# EnvironmentMonitorV3.net
KiCad netlist of a schematic drawn in EAGLE
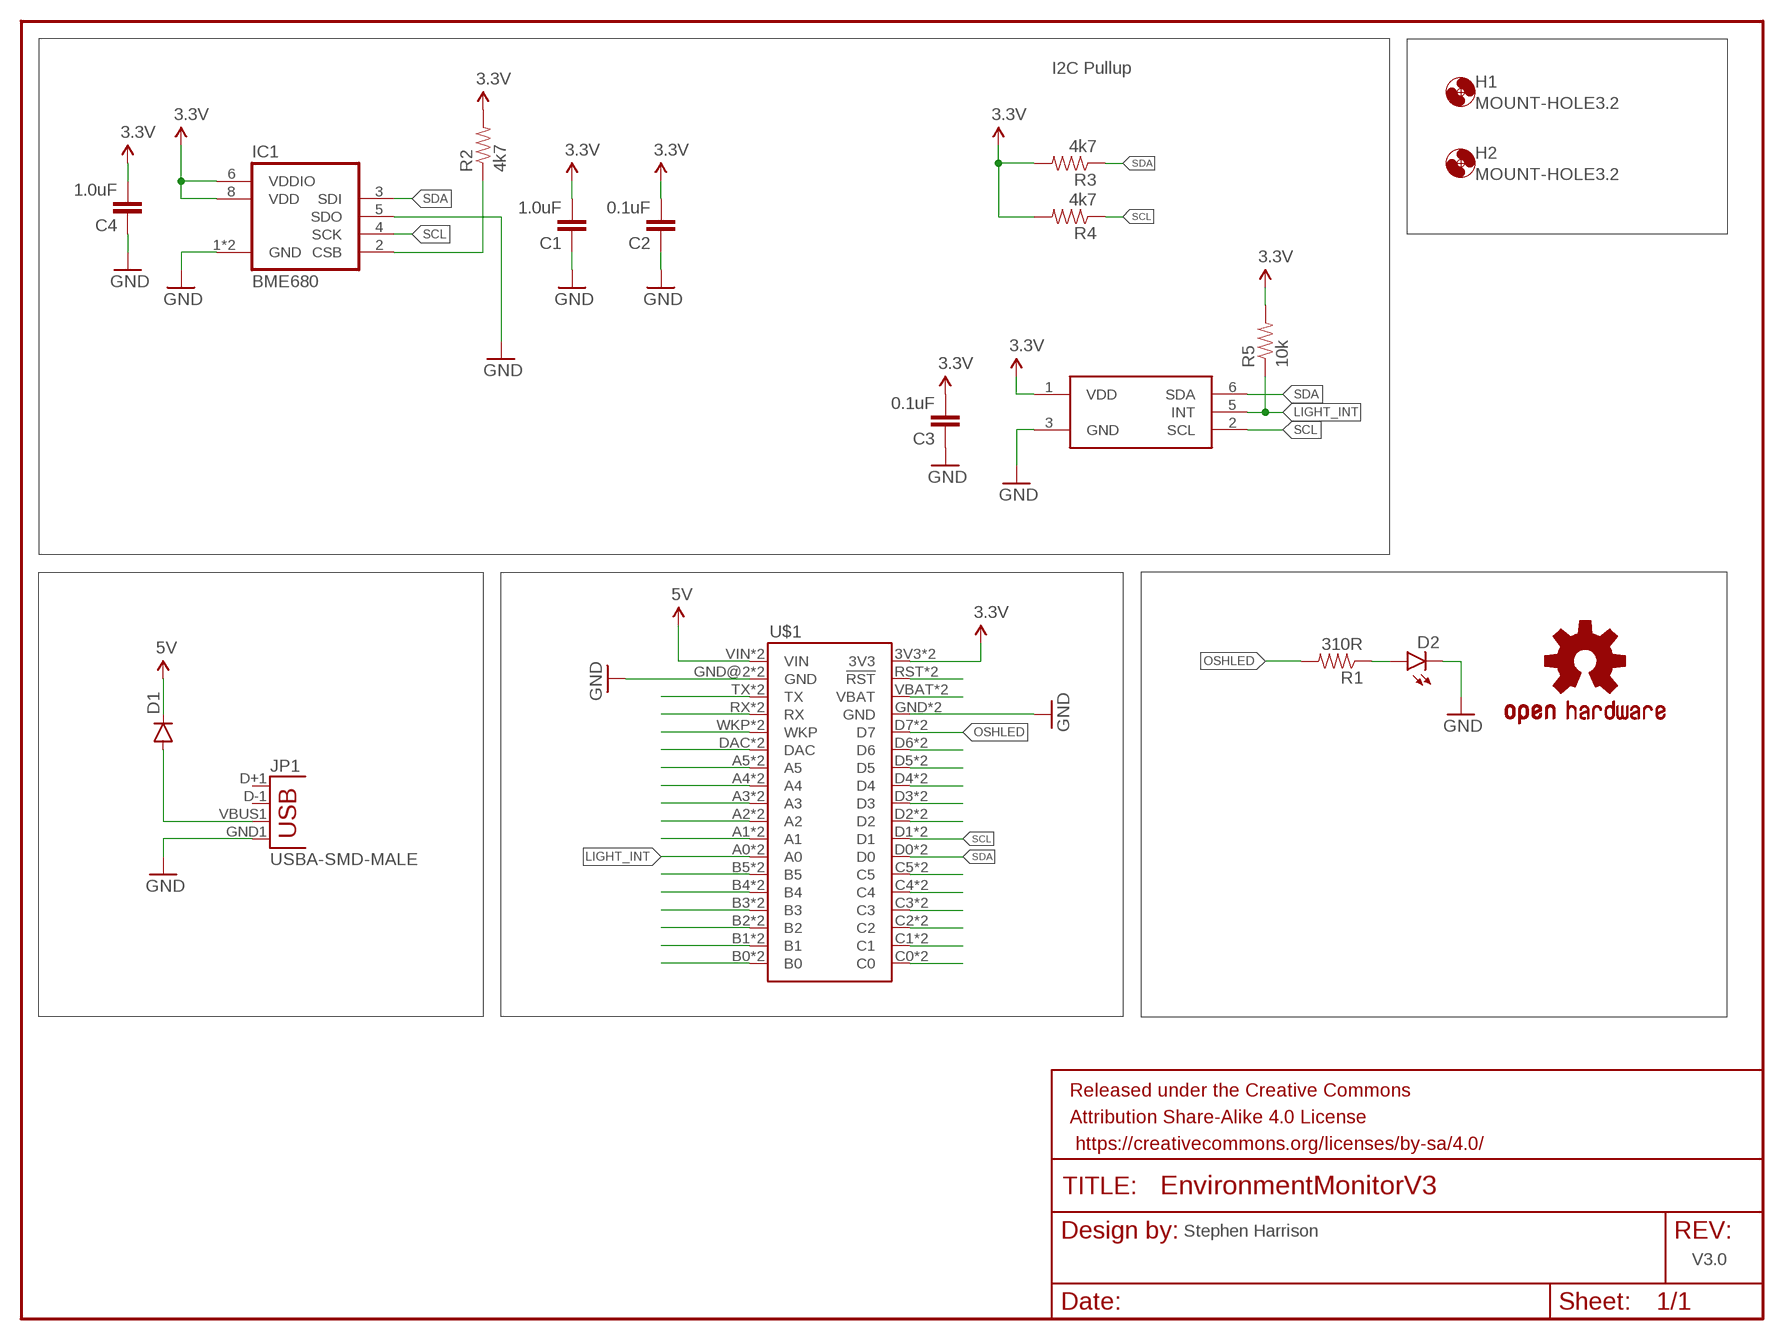
[diagram p0: schematic, sheet 1]

(export (version "E")
  (design (tool "Eeschema 10.0.6"))
  (components
    (comp (ref "C1")
      (value "1.0uF")
      (footprint "eagle-import:0805-CAP")
      (libsource (lib "eagle-import") (part "1.0UF-25V-+80/-20(0805){dblquote}"))
    )
    (comp (ref "C2")
      (value "0.1uF")
      (footprint "eagle-import:0805-CAP")
      (libsource (lib "eagle-import") (part "1.0UF-25V-+80/-20(0805){dblquote}"))
    )
    (comp (ref "C3")
      (value "0.1uF")
      (footprint "eagle-import:0805-CAP")
      (libsource (lib "eagle-import") (part "1.0UF-25V-+80/-20(0805){dblquote}"))
    )
    (comp (ref "C4")
      (value "1.0uF")
      (footprint "eagle-import:0805-CAP")
      (libsource (lib "eagle-import") (part "1.0UF-25V-+80/-20(0805){dblquote}"))
    )
    (comp (ref "D1")
      (value "DIODESMA")
      (footprint "eagle-import:SMA-DIODE")
      (libsource (lib "eagle-import") (part "DIODESMA"))
    )
    (comp (ref "D2")
      (value "LED1206-BOTTOM")
      (footprint "eagle-import:LED-1206-BOTTOM")
      (libsource (lib "eagle-import") (part "LED1206-BOTTOM"))
    )
    (comp (ref "FRAME1")
      (value "FRAME-LETTER")
      (footprint "eagle-import:CREATIVE_COMMONS")
      (libsource (lib "eagle-import") (part "FRAME-LETTER"))
    )
    (comp (ref "H1")
      (value "MOUNT-HOLE3.2")
      (footprint "eagle-import:3,2")
      (libsource (lib "eagle-import") (part "MOUNT-HOLE3.2"))
    )
    (comp (ref "H2")
      (value "MOUNT-HOLE3.2")
      (footprint "eagle-import:3,2")
      (libsource (lib "eagle-import") (part "MOUNT-HOLE3.2"))
    )
    (comp (ref "IC1")
      (value "BME680")
      (footprint "eagle-import:BME680")
      (libsource (lib "eagle-import") (part "BME680"))
    )
    (comp (ref "JP1")
      (value "USBA-SMD-MALE")
      (footprint "eagle-import:USB-A-SMT-MALE")
      (libsource (lib "eagle-import") (part "USBA-SMD-MALE"))
    )
    (comp (ref "LOGO1")
      (value "OSHW-LOGOM")
      (footprint "eagle-import:OSHW-LOGO-M")
      (libsource (lib "eagle-import") (part "OSHW-LOGOM"))
    )
    (comp (ref "R1")
      (value "310R")
      (footprint "eagle-import:0805")
      (libsource (lib "eagle-import") (part "RESISTOR0805-RES"))
    )
    (comp (ref "R2")
      (value "4k7")
      (footprint "eagle-import:0805")
      (libsource (lib "eagle-import") (part "RESISTOR0805-RES"))
    )
    (comp (ref "R3")
      (value "4k7")
      (footprint "eagle-import:0805")
      (libsource (lib "eagle-import") (part "RESISTOR0805-RES"))
    )
    (comp (ref "R4")
      (value "4k7")
      (footprint "eagle-import:0805")
      (libsource (lib "eagle-import") (part "RESISTOR0805-RES"))
    )
    (comp (ref "R5")
      (value "10k")
      (footprint "eagle-import:0805")
      (libsource (lib "eagle-import") (part "RESISTOR0805-RES"))
    )
    (comp (ref "U$1")
      (value "ELECTRONDUALNAMED")
      (footprint "eagle-import:ELECTRON_SIMPLE_SILK_NAMES_DUAL")
      (libsource (lib "eagle-import") (part "ELECTRONDUALNAMED"))
    )
    (comp (ref "U$2")
      (value "TCS3472")
      (footprint "eagle-import:FN-6")
      (libsource (lib "eagle-import") (part "TCS3472"))
    )
  )
  (nets
    (net (code "1") (name "3.3V") (class "Default")
      (node (ref "C1") (pin "2") (pinfunction "2_2") (pintype "passive"))
      (node (ref "C2") (pin "2") (pinfunction "2_2") (pintype "passive"))
      (node (ref "C3") (pin "2") (pinfunction "2_2") (pintype "passive"))
      (node (ref "C4") (pin "2") (pinfunction "2_2") (pintype "passive"))
      (node (ref "IC1") (pin "6") (pinfunction "VDDIO_6") (pintype "power_in"))
      (node (ref "IC1") (pin "8") (pinfunction "VDD_8") (pintype "power_in"))
      (node (ref "R2") (pin "2") (pinfunction "2_2") (pintype "passive"))
      (node (ref "R3") (pin "2") (pinfunction "2_2") (pintype "passive"))
      (node (ref "R4") (pin "2") (pinfunction "2_2") (pintype "passive"))
      (node (ref "R5") (pin "2") (pinfunction "2_2") (pintype "passive"))
      (node (ref "U$1") (pin "3V3") (pinfunction "3V3_3V3") (pintype "power_in"))
      (node (ref "U$1") (pin "3V3_1") (pinfunction "3V3_3V3_1") (pintype "power_in"))
      (node (ref "U$2") (pin "1") (pinfunction "VDD_1") (pintype "bidirectional"))
    )
    (net (code "2") (name "5V") (class "Default")
      (node (ref "D1") (pin "C") (pinfunction "C_C") (pintype "passive"))
      (node (ref "U$1") (pin "VIN") (pinfunction "VIN_VIN") (pintype "power_in"))
      (node (ref "U$1") (pin "VIN_1B") (pinfunction "VIN_VIN_1B") (pintype "power_in"))
    )
    (net (code "3") (name "GND") (class "Default")
      (node (ref "C1") (pin "1") (pinfunction "1_1") (pintype "passive"))
      (node (ref "C2") (pin "1") (pinfunction "1_1") (pintype "passive"))
      (node (ref "C3") (pin "1") (pinfunction "1_1") (pintype "passive"))
      (node (ref "C4") (pin "1") (pinfunction "1_1") (pintype "passive"))
      (node (ref "D2") (pin "C") (pinfunction "C_C") (pintype "passive"))
      (node (ref "IC1") (pin "1") (pinfunction "GND_1") (pintype "power_in"))
      (node (ref "IC1") (pin "5") (pinfunction "SDO_5") (pintype "output"))
      (node (ref "IC1") (pin "7") (pinfunction "GND_7") (pintype "power_in"))
      (node (ref "JP1") (pin "GND1") (pinfunction "GND_GND1") (pintype "bidirectional"))
      (node (ref "U$1") (pin "GND") (pinfunction "GND_GND") (pintype "power_in"))
      (node (ref "U$1") (pin "GND@2") (pinfunction "GND_GND@2") (pintype "power_in"))
      (node (ref "U$1") (pin "GND_1") (pinfunction "GND_GND_1") (pintype "power_in"))
      (node (ref "U$1") (pin "GND_1B") (pinfunction "GND_GND_1B") (pintype "power_in"))
      (node (ref "U$2") (pin "3") (pinfunction "GND_3") (pintype "bidirectional"))
    )
    (net (code "4") (name "LIGHT_INT") (class "Default")
      (node (ref "R5") (pin "1") (pinfunction "1_1") (pintype "passive"))
      (node (ref "U$1") (pin "A0") (pinfunction "A0_A0") (pintype "bidirectional"))
      (node (ref "U$1") (pin "A0_1") (pinfunction "A0_A0_1") (pintype "bidirectional"))
      (node (ref "U$2") (pin "5") (pinfunction "INT_5") (pintype "bidirectional"))
    )
    (net (code "5") (name "Net-(D2-PadA)") (class "Default")
      (node (ref "D2") (pin "A") (pinfunction "A_A") (pintype "passive"))
      (node (ref "R1") (pin "1") (pinfunction "1_1") (pintype "passive"))
    )
    (net (code "6") (name "Net-(IC1-CSB)") (class "Default")
      (node (ref "IC1") (pin "2") (pinfunction "CSB_2") (pintype "input"))
      (node (ref "R2") (pin "1") (pinfunction "1_1") (pintype "passive"))
    )
    (net (code "7") (name "Net-(JP1-VBUS)") (class "Default")
      (node (ref "D1") (pin "A") (pinfunction "A_A") (pintype "passive"))
      (node (ref "JP1") (pin "VBUS1") (pinfunction "VBUS_VBUS1") (pintype "bidirectional"))
    )
    (net (code "8") (name "Net-(U$1-A1-PadA1_1)") (class "Default")
      (node (ref "U$1") (pin "A1") (pinfunction "A1_A1") (pintype "bidirectional"))
      (node (ref "U$1") (pin "A1_1") (pinfunction "A1_A1_1") (pintype "bidirectional"))
    )
    (net (code "9") (name "Net-(U$1-A2-PadA2_1)") (class "Default")
      (node (ref "U$1") (pin "A2") (pinfunction "A2_A2") (pintype "bidirectional"))
      (node (ref "U$1") (pin "A2_1") (pinfunction "A2_A2_1") (pintype "bidirectional"))
    )
    (net (code "10") (name "Net-(U$1-A3-PadA3_1)") (class "Default")
      (node (ref "U$1") (pin "A3") (pinfunction "A3_A3") (pintype "bidirectional"))
      (node (ref "U$1") (pin "A3_1") (pinfunction "A3_A3_1") (pintype "bidirectional"))
    )
    (net (code "11") (name "Net-(U$1-A4-PadA4_1)") (class "Default")
      (node (ref "U$1") (pin "A4") (pinfunction "A4_A4") (pintype "bidirectional"))
      (node (ref "U$1") (pin "A4_1") (pinfunction "A4_A4_1") (pintype "bidirectional"))
    )
    (net (code "12") (name "Net-(U$1-A5-PadA5_1)") (class "Default")
      (node (ref "U$1") (pin "A5") (pinfunction "A5_A5") (pintype "bidirectional"))
      (node (ref "U$1") (pin "A5_1") (pinfunction "A5_A5_1") (pintype "bidirectional"))
    )
    (net (code "13") (name "Net-(U$1-B0-PadB0_1)") (class "Default")
      (node (ref "U$1") (pin "B0") (pinfunction "B0_B0") (pintype "bidirectional"))
      (node (ref "U$1") (pin "B0_1") (pinfunction "B0_B0_1") (pintype "bidirectional"))
    )
    (net (code "14") (name "Net-(U$1-B1-PadB1_1)") (class "Default")
      (node (ref "U$1") (pin "B1") (pinfunction "B1_B1") (pintype "bidirectional"))
      (node (ref "U$1") (pin "B1_1") (pinfunction "B1_B1_1") (pintype "bidirectional"))
    )
    (net (code "15") (name "Net-(U$1-B2-PadB2_1)") (class "Default")
      (node (ref "U$1") (pin "B2") (pinfunction "B2_B2") (pintype "bidirectional"))
      (node (ref "U$1") (pin "B2_1") (pinfunction "B2_B2_1") (pintype "bidirectional"))
    )
    (net (code "16") (name "Net-(U$1-B3-PadB3_1)") (class "Default")
      (node (ref "U$1") (pin "B3") (pinfunction "B3_B3") (pintype "bidirectional"))
      (node (ref "U$1") (pin "B3_1") (pinfunction "B3_B3_1") (pintype "bidirectional"))
    )
    (net (code "17") (name "Net-(U$1-B4-PadB4_1)") (class "Default")
      (node (ref "U$1") (pin "B4") (pinfunction "B4_B4") (pintype "bidirectional"))
      (node (ref "U$1") (pin "B4_1") (pinfunction "B4_B4_1") (pintype "bidirectional"))
    )
    (net (code "18") (name "Net-(U$1-B5-PadB5_1)") (class "Default")
      (node (ref "U$1") (pin "B5") (pinfunction "B5_B5") (pintype "bidirectional"))
      (node (ref "U$1") (pin "B5_1") (pinfunction "B5_B5_1") (pintype "bidirectional"))
    )
    (net (code "19") (name "Net-(U$1-C0-PadC0_1)") (class "Default")
      (node (ref "U$1") (pin "C0") (pinfunction "C0_C0") (pintype "bidirectional"))
      (node (ref "U$1") (pin "C0_1") (pinfunction "C0_C0_1") (pintype "bidirectional"))
    )
    (net (code "20") (name "Net-(U$1-C1-PadC1_1)") (class "Default")
      (node (ref "U$1") (pin "C1") (pinfunction "C1_C1") (pintype "bidirectional"))
      (node (ref "U$1") (pin "C1_1") (pinfunction "C1_C1_1") (pintype "bidirectional"))
    )
    (net (code "21") (name "Net-(U$1-C2-PadC2_1)") (class "Default")
      (node (ref "U$1") (pin "C2") (pinfunction "C2_C2") (pintype "bidirectional"))
      (node (ref "U$1") (pin "C2_1") (pinfunction "C2_C2_1") (pintype "bidirectional"))
    )
    (net (code "22") (name "Net-(U$1-C3-PadC3_1)") (class "Default")
      (node (ref "U$1") (pin "C3") (pinfunction "C3_C3") (pintype "bidirectional"))
      (node (ref "U$1") (pin "C3_1") (pinfunction "C3_C3_1") (pintype "bidirectional"))
    )
    (net (code "23") (name "Net-(U$1-C4-PadC4_1)") (class "Default")
      (node (ref "U$1") (pin "C4") (pinfunction "C4_C4") (pintype "bidirectional"))
      (node (ref "U$1") (pin "C4_1") (pinfunction "C4_C4_1") (pintype "bidirectional"))
    )
    (net (code "24") (name "Net-(U$1-C5-PadC5_1)") (class "Default")
      (node (ref "U$1") (pin "C5") (pinfunction "C5_C5") (pintype "bidirectional"))
      (node (ref "U$1") (pin "C5_1") (pinfunction "C5_C5_1") (pintype "bidirectional"))
    )
    (net (code "25") (name "Net-(U$1-D2-PadD2_1)") (class "Default")
      (node (ref "U$1") (pin "D2") (pinfunction "D2_D2") (pintype "bidirectional"))
      (node (ref "U$1") (pin "D2_1") (pinfunction "D2_D2_1") (pintype "bidirectional"))
    )
    (net (code "26") (name "Net-(U$1-D3-PadD3_1)") (class "Default")
      (node (ref "U$1") (pin "D3") (pinfunction "D3_D3") (pintype "bidirectional"))
      (node (ref "U$1") (pin "D3_1") (pinfunction "D3_D3_1") (pintype "bidirectional"))
    )
    (net (code "27") (name "Net-(U$1-D4-PadD4_1)") (class "Default")
      (node (ref "U$1") (pin "D4") (pinfunction "D4_D4") (pintype "bidirectional"))
      (node (ref "U$1") (pin "D4_1") (pinfunction "D4_D4_1") (pintype "bidirectional"))
    )
    (net (code "28") (name "Net-(U$1-D5-PadD5_1)") (class "Default")
      (node (ref "U$1") (pin "D5") (pinfunction "D5_D5") (pintype "bidirectional"))
      (node (ref "U$1") (pin "D5_1") (pinfunction "D5_D5_1") (pintype "bidirectional"))
    )
    (net (code "29") (name "Net-(U$1-D6-PadD6_1)") (class "Default")
      (node (ref "U$1") (pin "D6") (pinfunction "D6_D6") (pintype "bidirectional"))
      (node (ref "U$1") (pin "D6_1") (pinfunction "D6_D6_1") (pintype "bidirectional"))
    )
    (net (code "30") (name "Net-(U$1-DAC-PadDAC_1)") (class "Default")
      (node (ref "U$1") (pin "DAC") (pinfunction "DAC_DAC") (pintype "bidirectional"))
      (node (ref "U$1") (pin "DAC_1") (pinfunction "DAC_DAC_1") (pintype "bidirectional"))
    )
    (net (code "31") (name "Net-(U$1-PadRX)") (class "Default")
      (node (ref "U$1") (pin "RX") (pinfunction "RX_RX") (pintype "bidirectional"))
      (node (ref "U$1") (pin "RX_1") (pinfunction "RX_RX_1") (pintype "bidirectional"))
    )
    (net (code "32") (name "Net-(U$1-PadTX)") (class "Default")
      (node (ref "U$1") (pin "TX") (pinfunction "TX_TX") (pintype "bidirectional"))
      (node (ref "U$1") (pin "TX_1") (pinfunction "TX_TX_1") (pintype "bidirectional"))
    )
    (net (code "33") (name "Net-(U$1-PadVBAT)") (class "Default")
      (node (ref "U$1") (pin "VBAT") (pinfunction "VBAT_VBAT") (pintype "passive"))
      (node (ref "U$1") (pin "VBATT_1") (pinfunction "VBAT_VBATT_1") (pintype "passive"))
    )
    (net (code "34") (name "Net-(U$1-PadWKP)") (class "Default")
      (node (ref "U$1") (pin "WKP") (pinfunction "WKP_WKP") (pintype "bidirectional"))
      (node (ref "U$1") (pin "WKP_1") (pinfunction "WKP_WKP_1") (pintype "bidirectional"))
    )
    (net (code "35") (name "Net-(U$1-~{RST}-PadRST)") (class "Default")
      (node (ref "U$1") (pin "RST") (pinfunction "~{RST}_RST") (pintype "bidirectional"))
      (node (ref "U$1") (pin "RST_1") (pinfunction "~{RST}_RST_1") (pintype "bidirectional"))
    )
    (net (code "36") (name "OSHLED") (class "Default")
      (node (ref "R1") (pin "2") (pinfunction "2_2") (pintype "passive"))
      (node (ref "U$1") (pin "D7") (pinfunction "D7_D7") (pintype "bidirectional"))
      (node (ref "U$1") (pin "D7_1") (pinfunction "D7_D7_1") (pintype "bidirectional"))
    )
    (net (code "37") (name "SCL") (class "Default")
      (node (ref "IC1") (pin "4") (pinfunction "SCK_4") (pintype "input"))
      (node (ref "R4") (pin "1") (pinfunction "1_1") (pintype "passive"))
      (node (ref "U$1") (pin "D1") (pinfunction "D1_D1") (pintype "bidirectional"))
      (node (ref "U$1") (pin "D1_1") (pinfunction "D1_D1_1") (pintype "bidirectional"))
      (node (ref "U$2") (pin "2") (pinfunction "SCL_2") (pintype "bidirectional"))
    )
    (net (code "38") (name "SDA") (class "Default")
      (node (ref "IC1") (pin "3") (pinfunction "SDI_3") (pintype "input"))
      (node (ref "R3") (pin "1") (pinfunction "1_1") (pintype "passive"))
      (node (ref "U$1") (pin "D0") (pinfunction "D0_D0") (pintype "bidirectional"))
      (node (ref "U$1") (pin "D0_1") (pinfunction "D0_D0_1") (pintype "bidirectional"))
      (node (ref "U$2") (pin "6") (pinfunction "SDA_6") (pintype "bidirectional"))
    )
    (net (code "39") (name "unconnected-(JP1-D+-PadD+1)") (class "Default")
      (node (ref "JP1") (pin "D+1") (pinfunction "D+_D+1") (pintype "bidirectional"))
    )
    (net (code "40") (name "unconnected-(JP1-D--PadD-1)") (class "Default")
      (node (ref "JP1") (pin "D-1") (pinfunction "D-_D-1") (pintype "bidirectional"))
    )
  )
)
